# Key.net
KiCad netlist of a schematic drawn in Altium Designer
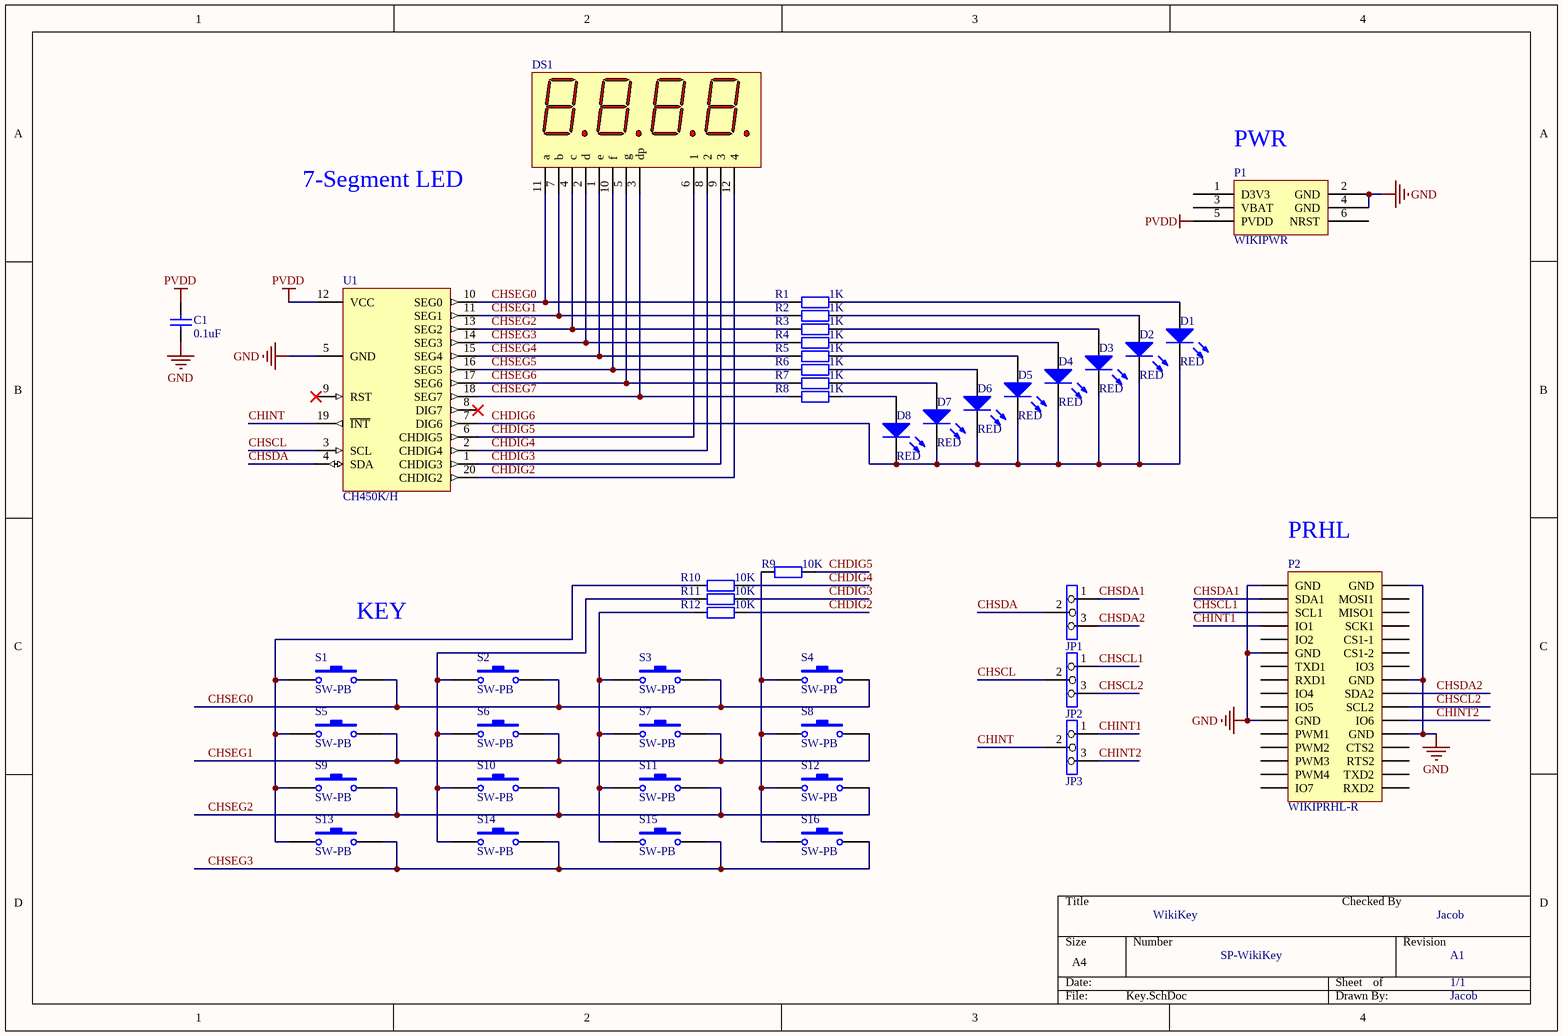
[diagram p0: Key.SchDoc]

(export (version "E")
  (design (tool "Eeschema 10.0.6"))
  (components
    (comp (ref "C1")
      (value "0.1uF")
      (footprint "0603M")
      (description "Capacitor")
      (fields (field (name "PUBLISHER") "Altium Limited"))
      (libsource (lib "Miscellaneous Devices") (part "Cap"))
    )
    (comp (ref "D1")
      (value "RED")
      (footprint "0603pn")
      (description "Typical INFRARED GaAs LED")
      (fields (field (name "PUBLISHER") "Altium Limited"))
      (libsource (lib "Miscellaneous Devices") (part "LED0"))
    )
    (comp (ref "D2")
      (value "RED")
      (footprint "0603pn")
      (description "Typical INFRARED GaAs LED")
      (fields (field (name "PUBLISHER") "Altium Limited"))
      (libsource (lib "Miscellaneous Devices") (part "LED0"))
    )
    (comp (ref "D3")
      (value "RED")
      (footprint "0603pn")
      (description "Typical INFRARED GaAs LED")
      (fields (field (name "PUBLISHER") "Altium Limited"))
      (libsource (lib "Miscellaneous Devices") (part "LED0"))
    )
    (comp (ref "D4")
      (value "RED")
      (footprint "0603pn")
      (description "Typical INFRARED GaAs LED")
      (fields (field (name "PUBLISHER") "Altium Limited"))
      (libsource (lib "Miscellaneous Devices") (part "LED0"))
    )
    (comp (ref "D5")
      (value "RED")
      (footprint "0603pn")
      (description "Typical INFRARED GaAs LED")
      (fields (field (name "PUBLISHER") "Altium Limited"))
      (libsource (lib "Miscellaneous Devices") (part "LED0"))
    )
    (comp (ref "D6")
      (value "RED")
      (footprint "0603pn")
      (description "Typical INFRARED GaAs LED")
      (fields (field (name "PUBLISHER") "Altium Limited"))
      (libsource (lib "Miscellaneous Devices") (part "LED0"))
    )
    (comp (ref "D7")
      (value "RED")
      (footprint "0603pn")
      (description "Typical INFRARED GaAs LED")
      (fields (field (name "PUBLISHER") "Altium Limited"))
      (libsource (lib "Miscellaneous Devices") (part "LED0"))
    )
    (comp (ref "D8")
      (value "RED")
      (footprint "0603pn")
      (description "Typical INFRARED GaAs LED")
      (fields (field (name "PUBLISHER") "Altium Limited"))
      (libsource (lib "Miscellaneous Devices") (part "LED0"))
    )
    (comp (ref "DS1")
      (value "7SEG-4")
      (footprint "7SGLED-4-0.28")
      (description "Black Surface HER 7-Segment Display")
      (fields (field (name "PUBLISHER") "Altium Limited"))
      (libsource (lib "Misc") (part "7SEG-4"))
    )
    (comp (ref "JP1") (value "Jumper3") (footprint "HDR1X3/2.54MM") (libsource (lib "Misc") (part "Jumper3")))
    (comp (ref "JP2") (value "Jumper3") (footprint "HDR1X3/2.54MM") (libsource (lib "Misc") (part "Jumper3")))
    (comp (ref "JP3") (value "Jumper3") (footprint "HDR1X3/2.54MM") (libsource (lib "Misc") (part "Jumper3")))
    (comp (ref "P1")
      (value "WIKIPWR")
      (footprint "WIKIPWR")
      (description "PWR HDR")
      (libsource (lib "Connector") (part "WIKIPWR"))
    )
    (comp (ref "P2")
      (value "WIKIPRHL-R")
      (footprint "HDR2X16-WIKIPRHL-R")
      (description "Header, 16-Pin, Dual row")
      (fields (field (name "PUBLISHER") "Altium Limited"))
      (libsource (lib "Connector") (part "WIKIPRHL-R"))
    )
    (comp (ref "R1")
      (value "1K")
      (footprint "0603M")
      (description "Resistor")
      (fields (field (name "PUBLISHER") "Altium Limited"))
      (libsource (lib "Miscellaneous Devices") (part "Res2"))
    )
    (comp (ref "R2")
      (value "1K")
      (footprint "0603M")
      (description "Resistor")
      (fields (field (name "PUBLISHER") "Altium Limited"))
      (libsource (lib "Miscellaneous Devices") (part "Res2"))
    )
    (comp (ref "R3")
      (value "1K")
      (footprint "0603M")
      (description "Resistor")
      (fields (field (name "PUBLISHER") "Altium Limited"))
      (libsource (lib "Miscellaneous Devices") (part "Res2"))
    )
    (comp (ref "R4")
      (value "1K")
      (footprint "0603M")
      (description "Resistor")
      (fields (field (name "PUBLISHER") "Altium Limited"))
      (libsource (lib "Miscellaneous Devices") (part "Res2"))
    )
    (comp (ref "R5")
      (value "1K")
      (footprint "0603M")
      (description "Resistor")
      (fields (field (name "PUBLISHER") "Altium Limited"))
      (libsource (lib "Miscellaneous Devices") (part "Res2"))
    )
    (comp (ref "R6")
      (value "1K")
      (footprint "0603M")
      (description "Resistor")
      (fields (field (name "PUBLISHER") "Altium Limited"))
      (libsource (lib "Miscellaneous Devices") (part "Res2"))
    )
    (comp (ref "R7")
      (value "1K")
      (footprint "0603M")
      (description "Resistor")
      (fields (field (name "PUBLISHER") "Altium Limited"))
      (libsource (lib "Miscellaneous Devices") (part "Res2"))
    )
    (comp (ref "R8")
      (value "1K")
      (footprint "0603M")
      (description "Resistor")
      (fields (field (name "PUBLISHER") "Altium Limited"))
      (libsource (lib "Miscellaneous Devices") (part "Res2"))
    )
    (comp (ref "R9")
      (value "10K")
      (footprint "0603M")
      (description "Resistor")
      (fields (field (name "PUBLISHER") "Altium Limited"))
      (libsource (lib "Miscellaneous Devices") (part "Res2"))
    )
    (comp (ref "R10")
      (value "10K")
      (footprint "0603M")
      (description "Resistor")
      (fields (field (name "PUBLISHER") "Altium Limited"))
      (libsource (lib "Miscellaneous Devices") (part "Res2"))
    )
    (comp (ref "R11")
      (value "10K")
      (footprint "0603M")
      (description "Resistor")
      (fields (field (name "PUBLISHER") "Altium Limited"))
      (libsource (lib "Miscellaneous Devices") (part "Res2"))
    )
    (comp (ref "R12")
      (value "10K")
      (footprint "0603M")
      (description "Resistor")
      (fields (field (name "PUBLISHER") "Altium Limited"))
      (libsource (lib "Miscellaneous Devices") (part "Res2"))
    )
    (comp (ref "S1")
      (value "SW-PB")
      (footprint "KEY-4.5X4.5-SMD")
      (description "Switch")
      (fields (field (name "PUBLISHER") "Altium Limited"))
      (libsource (lib "CT107D_SUDA") (part "SW-PB"))
    )
    (comp (ref "S2")
      (value "SW-PB")
      (footprint "KEY-4.5X4.5-SMD")
      (description "Switch")
      (fields (field (name "PUBLISHER") "Altium Limited"))
      (libsource (lib "CT107D_SUDA") (part "SW-PB"))
    )
    (comp (ref "S3")
      (value "SW-PB")
      (footprint "KEY-4.5X4.5-SMD")
      (description "Switch")
      (fields (field (name "PUBLISHER") "Altium Limited"))
      (libsource (lib "CT107D_SUDA") (part "SW-PB"))
    )
    (comp (ref "S4")
      (value "SW-PB")
      (footprint "KEY-4.5X4.5-SMD")
      (description "Switch")
      (fields (field (name "PUBLISHER") "Altium Limited"))
      (libsource (lib "CT107D_SUDA") (part "SW-PB"))
    )
    (comp (ref "S5")
      (value "SW-PB")
      (footprint "KEY-4.5X4.5-SMD")
      (description "Switch")
      (fields (field (name "PUBLISHER") "Altium Limited"))
      (libsource (lib "CT107D_SUDA") (part "SW-PB"))
    )
    (comp (ref "S6")
      (value "SW-PB")
      (footprint "KEY-4.5X4.5-SMD")
      (description "Switch")
      (fields (field (name "PUBLISHER") "Altium Limited"))
      (libsource (lib "CT107D_SUDA") (part "SW-PB"))
    )
    (comp (ref "S7")
      (value "SW-PB")
      (footprint "KEY-4.5X4.5-SMD")
      (description "Switch")
      (fields (field (name "PUBLISHER") "Altium Limited"))
      (libsource (lib "CT107D_SUDA") (part "SW-PB"))
    )
    (comp (ref "S8")
      (value "SW-PB")
      (footprint "KEY-4.5X4.5-SMD")
      (description "Switch")
      (fields (field (name "PUBLISHER") "Altium Limited"))
      (libsource (lib "CT107D_SUDA") (part "SW-PB"))
    )
    (comp (ref "S9")
      (value "SW-PB")
      (footprint "KEY-4.5X4.5-SMD")
      (description "Switch")
      (fields (field (name "PUBLISHER") "Altium Limited"))
      (libsource (lib "CT107D_SUDA") (part "SW-PB"))
    )
    (comp (ref "S10")
      (value "SW-PB")
      (footprint "KEY-4.5X4.5-SMD")
      (description "Switch")
      (fields (field (name "PUBLISHER") "Altium Limited"))
      (libsource (lib "CT107D_SUDA") (part "SW-PB"))
    )
    (comp (ref "S11")
      (value "SW-PB")
      (footprint "KEY-4.5X4.5-SMD")
      (description "Switch")
      (fields (field (name "PUBLISHER") "Altium Limited"))
      (libsource (lib "CT107D_SUDA") (part "SW-PB"))
    )
    (comp (ref "S12")
      (value "SW-PB")
      (footprint "KEY-4.5X4.5-SMD")
      (description "Switch")
      (fields (field (name "PUBLISHER") "Altium Limited"))
      (libsource (lib "CT107D_SUDA") (part "SW-PB"))
    )
    (comp (ref "S13")
      (value "SW-PB")
      (footprint "KEY-4.5X4.5-SMD")
      (description "Switch")
      (fields (field (name "PUBLISHER") "Altium Limited"))
      (libsource (lib "CT107D_SUDA") (part "SW-PB"))
    )
    (comp (ref "S14")
      (value "SW-PB")
      (footprint "KEY-4.5X4.5-SMD")
      (description "Switch")
      (fields (field (name "PUBLISHER") "Altium Limited"))
      (libsource (lib "CT107D_SUDA") (part "SW-PB"))
    )
    (comp (ref "S15")
      (value "SW-PB")
      (footprint "KEY-4.5X4.5-SMD")
      (description "Switch")
      (fields (field (name "PUBLISHER") "Altium Limited"))
      (libsource (lib "CT107D_SUDA") (part "SW-PB"))
    )
    (comp (ref "S16")
      (value "SW-PB")
      (footprint "KEY-4.5X4.5-SMD")
      (description "Switch")
      (fields (field (name "PUBLISHER") "Altium Limited"))
      (libsource (lib "CT107D_SUDA") (part "SW-PB"))
    )
    (comp (ref "U1")
      (value "CH450K/H")
      (footprint "SO20W_M")
      (description "7 Segment LED& Key")
      (libsource (lib "Lunio") (part "CH450K/H"))
    )
  )
  (nets
    (net (code "1") (name "/CHDIG2") (class "Default")
      (node (ref "DS1") (pin "12") (pinfunction "4_12") (pintype "passive"))
      (node (ref "R12") (pin "1") (pinfunction "1_1") (pintype "passive"))
      (node (ref "U1") (pin "20") (pinfunction "CHDIG2_20") (pintype "output"))
    )
    (net (code "2") (name "/CHDIG3") (class "Default")
      (node (ref "DS1") (pin "9") (pinfunction "3_9") (pintype "passive"))
      (node (ref "R11") (pin "1") (pinfunction "1_1") (pintype "passive"))
      (node (ref "U1") (pin "1") (pinfunction "CHDIG3_1") (pintype "output"))
    )
    (net (code "3") (name "/CHDIG4") (class "Default")
      (node (ref "DS1") (pin "8") (pinfunction "2_8") (pintype "passive"))
      (node (ref "R10") (pin "1") (pinfunction "1_1") (pintype "passive"))
      (node (ref "U1") (pin "2") (pinfunction "CHDIG4_2") (pintype "output"))
    )
    (net (code "4") (name "/CHDIG5") (class "Default")
      (node (ref "DS1") (pin "6") (pinfunction "1_6") (pintype "passive"))
      (node (ref "R9") (pin "1") (pinfunction "1_1") (pintype "passive"))
      (node (ref "U1") (pin "6") (pinfunction "CHDIG5_6") (pintype "output"))
    )
    (net (code "5") (name "/CHDIG6") (class "Default")
      (node (ref "D1") (pin "2") (pinfunction "K_2") (pintype "passive"))
      (node (ref "D2") (pin "2") (pinfunction "K_2") (pintype "passive"))
      (node (ref "D3") (pin "2") (pinfunction "K_2") (pintype "passive"))
      (node (ref "D4") (pin "2") (pinfunction "K_2") (pintype "passive"))
      (node (ref "D5") (pin "2") (pinfunction "K_2") (pintype "passive"))
      (node (ref "D6") (pin "2") (pinfunction "K_2") (pintype "passive"))
      (node (ref "D7") (pin "2") (pinfunction "K_2") (pintype "passive"))
      (node (ref "D8") (pin "2") (pinfunction "K_2") (pintype "passive"))
      (node (ref "U1") (pin "7") (pinfunction "DIG6_7") (pintype "output"))
    )
    (net (code "6") (name "/CHINT") (class "Default")
      (node (ref "JP3") (pin "2") (pintype "passive"))
      (node (ref "U1") (pin "19") (pinfunction "~{INT}_19") (pintype "output"))
    )
    (net (code "7") (name "/CHINT1") (class "Default")
      (node (ref "JP3") (pin "1") (pintype "passive"))
      (node (ref "P2") (pin "7") (pinfunction "IO1_7") (pintype "passive"))
    )
    (net (code "8") (name "/CHINT2") (class "Default")
      (node (ref "JP3") (pin "3") (pintype "passive"))
      (node (ref "P2") (pin "22") (pinfunction "IO6_22") (pintype "passive"))
    )
    (net (code "9") (name "/CHSCL") (class "Default")
      (node (ref "JP2") (pin "2") (pintype "passive"))
      (node (ref "U1") (pin "3") (pinfunction "SCL_3") (pintype "input"))
    )
    (net (code "10") (name "/CHSCL1") (class "Default")
      (node (ref "JP2") (pin "1") (pintype "passive"))
      (node (ref "P2") (pin "5") (pinfunction "SCL1_5") (pintype "passive"))
    )
    (net (code "11") (name "/CHSCL2") (class "Default")
      (node (ref "JP2") (pin "3") (pintype "passive"))
      (node (ref "P2") (pin "20") (pinfunction "SCL2_20") (pintype "passive"))
    )
    (net (code "12") (name "/CHSDA") (class "Default")
      (node (ref "JP1") (pin "2") (pintype "passive"))
      (node (ref "U1") (pin "4") (pinfunction "SDA_4") (pintype "bidirectional"))
    )
    (net (code "13") (name "/CHSDA1") (class "Default")
      (node (ref "JP1") (pin "1") (pintype "passive"))
      (node (ref "P2") (pin "3") (pinfunction "SDA1_3") (pintype "passive"))
    )
    (net (code "14") (name "/CHSDA2") (class "Default")
      (node (ref "JP1") (pin "3") (pintype "passive"))
      (node (ref "P2") (pin "18") (pinfunction "SDA2_18") (pintype "passive"))
    )
    (net (code "15") (name "/CHSEG0") (class "Default")
      (node (ref "DS1") (pin "11") (pinfunction "a_11") (pintype "passive"))
      (node (ref "R1") (pin "2") (pinfunction "2_2") (pintype "passive"))
      (node (ref "S1") (pin "2") (pinfunction "2_2") (pintype "passive"))
      (node (ref "S2") (pin "2") (pinfunction "2_2") (pintype "passive"))
      (node (ref "S3") (pin "2") (pinfunction "2_2") (pintype "passive"))
      (node (ref "S4") (pin "2") (pinfunction "2_2") (pintype "passive"))
      (node (ref "U1") (pin "10") (pinfunction "SEG0_10") (pintype "output"))
    )
    (net (code "16") (name "/CHSEG1") (class "Default")
      (node (ref "DS1") (pin "7") (pinfunction "b_7") (pintype "passive"))
      (node (ref "R2") (pin "2") (pinfunction "2_2") (pintype "passive"))
      (node (ref "S5") (pin "2") (pinfunction "2_2") (pintype "passive"))
      (node (ref "S6") (pin "2") (pinfunction "2_2") (pintype "passive"))
      (node (ref "S7") (pin "2") (pinfunction "2_2") (pintype "passive"))
      (node (ref "S8") (pin "2") (pinfunction "2_2") (pintype "passive"))
      (node (ref "U1") (pin "11") (pinfunction "SEG1_11") (pintype "output"))
    )
    (net (code "17") (name "/CHSEG2") (class "Default")
      (node (ref "DS1") (pin "4") (pinfunction "c_4") (pintype "passive"))
      (node (ref "R3") (pin "2") (pinfunction "2_2") (pintype "passive"))
      (node (ref "S10") (pin "2") (pinfunction "2_2") (pintype "passive"))
      (node (ref "S11") (pin "2") (pinfunction "2_2") (pintype "passive"))
      (node (ref "S12") (pin "2") (pinfunction "2_2") (pintype "passive"))
      (node (ref "S9") (pin "2") (pinfunction "2_2") (pintype "passive"))
      (node (ref "U1") (pin "13") (pinfunction "SEG2_13") (pintype "output"))
    )
    (net (code "18") (name "/CHSEG3") (class "Default")
      (node (ref "DS1") (pin "2") (pinfunction "d_2") (pintype "passive"))
      (node (ref "R4") (pin "2") (pinfunction "2_2") (pintype "passive"))
      (node (ref "S13") (pin "2") (pinfunction "2_2") (pintype "passive"))
      (node (ref "S14") (pin "2") (pinfunction "2_2") (pintype "passive"))
      (node (ref "S15") (pin "2") (pinfunction "2_2") (pintype "passive"))
      (node (ref "S16") (pin "2") (pinfunction "2_2") (pintype "passive"))
      (node (ref "U1") (pin "14") (pinfunction "SEG3_14") (pintype "output"))
    )
    (net (code "19") (name "/CHSEG4") (class "Default")
      (node (ref "DS1") (pin "1") (pinfunction "e_1") (pintype "passive"))
      (node (ref "R5") (pin "2") (pinfunction "2_2") (pintype "passive"))
      (node (ref "U1") (pin "15") (pinfunction "SEG4_15") (pintype "output"))
    )
    (net (code "20") (name "/CHSEG5") (class "Default")
      (node (ref "DS1") (pin "10") (pinfunction "f_10") (pintype "passive"))
      (node (ref "R6") (pin "2") (pinfunction "2_2") (pintype "passive"))
      (node (ref "U1") (pin "16") (pinfunction "SEG5_16") (pintype "output"))
    )
    (net (code "21") (name "/CHSEG6") (class "Default")
      (node (ref "DS1") (pin "5") (pinfunction "g_5") (pintype "passive"))
      (node (ref "R7") (pin "2") (pinfunction "2_2") (pintype "passive"))
      (node (ref "U1") (pin "17") (pinfunction "SEG6_17") (pintype "output"))
    )
    (net (code "22") (name "/CHSEG7") (class "Default")
      (node (ref "DS1") (pin "3") (pinfunction "dp_3") (pintype "passive"))
      (node (ref "R8") (pin "2") (pinfunction "2_2") (pintype "passive"))
      (node (ref "U1") (pin "18") (pinfunction "SEG7_18") (pintype "output"))
    )
    (net (code "23") (name "GND") (class "Default")
      (node (ref "C1") (pin "1") (pinfunction "1_1") (pintype "passive"))
      (node (ref "P1") (pin "2") (pinfunction "GND_2") (pintype "passive"))
      (node (ref "P1") (pin "4") (pinfunction "GND_4") (pintype "passive"))
      (node (ref "P2") (pin "1") (pinfunction "GND_1") (pintype "passive"))
      (node (ref "P2") (pin "11") (pinfunction "GND_11") (pintype "passive"))
      (node (ref "P2") (pin "16") (pinfunction "GND_16") (pintype "passive"))
      (node (ref "P2") (pin "2") (pinfunction "GND_2") (pintype "passive"))
      (node (ref "P2") (pin "21") (pinfunction "GND_21") (pintype "passive"))
      (node (ref "P2") (pin "24") (pinfunction "GND_24") (pintype "passive"))
      (node (ref "U1") (pin "5") (pinfunction "GND_5") (pintype "power_in"))
    )
    (net (code "24") (name "Net-(D1-A)") (class "Default")
      (node (ref "D1") (pin "1") (pinfunction "A_1") (pintype "passive"))
      (node (ref "R1") (pin "1") (pinfunction "1_1") (pintype "passive"))
    )
    (net (code "25") (name "Net-(D2-A)") (class "Default")
      (node (ref "D2") (pin "1") (pinfunction "A_1") (pintype "passive"))
      (node (ref "R2") (pin "1") (pinfunction "1_1") (pintype "passive"))
    )
    (net (code "26") (name "Net-(D3-A)") (class "Default")
      (node (ref "D3") (pin "1") (pinfunction "A_1") (pintype "passive"))
      (node (ref "R3") (pin "1") (pinfunction "1_1") (pintype "passive"))
    )
    (net (code "27") (name "Net-(D4-A)") (class "Default")
      (node (ref "D4") (pin "1") (pinfunction "A_1") (pintype "passive"))
      (node (ref "R4") (pin "1") (pinfunction "1_1") (pintype "passive"))
    )
    (net (code "28") (name "Net-(D5-A)") (class "Default")
      (node (ref "D5") (pin "1") (pinfunction "A_1") (pintype "passive"))
      (node (ref "R5") (pin "1") (pinfunction "1_1") (pintype "passive"))
    )
    (net (code "29") (name "Net-(D6-A)") (class "Default")
      (node (ref "D6") (pin "1") (pinfunction "A_1") (pintype "passive"))
      (node (ref "R6") (pin "1") (pinfunction "1_1") (pintype "passive"))
    )
    (net (code "30") (name "Net-(D7-A)") (class "Default")
      (node (ref "D7") (pin "1") (pinfunction "A_1") (pintype "passive"))
      (node (ref "R7") (pin "1") (pinfunction "1_1") (pintype "passive"))
    )
    (net (code "31") (name "Net-(D8-A)") (class "Default")
      (node (ref "D8") (pin "1") (pinfunction "A_1") (pintype "passive"))
      (node (ref "R8") (pin "1") (pinfunction "1_1") (pintype "passive"))
    )
    (net (code "32") (name "Net-(R9-Pad2)") (class "Default")
      (node (ref "R9") (pin "2") (pinfunction "2_2") (pintype "passive"))
      (node (ref "S12") (pin "1") (pinfunction "1_1") (pintype "passive"))
      (node (ref "S16") (pin "1") (pinfunction "1_1") (pintype "passive"))
      (node (ref "S4") (pin "1") (pinfunction "1_1") (pintype "passive"))
      (node (ref "S8") (pin "1") (pinfunction "1_1") (pintype "passive"))
    )
    (net (code "33") (name "Net-(R10-Pad2)") (class "Default")
      (node (ref "R10") (pin "2") (pinfunction "2_2") (pintype "passive"))
      (node (ref "S1") (pin "1") (pinfunction "1_1") (pintype "passive"))
      (node (ref "S13") (pin "1") (pinfunction "1_1") (pintype "passive"))
      (node (ref "S5") (pin "1") (pinfunction "1_1") (pintype "passive"))
      (node (ref "S9") (pin "1") (pinfunction "1_1") (pintype "passive"))
    )
    (net (code "34") (name "Net-(R11-Pad2)") (class "Default")
      (node (ref "R11") (pin "2") (pinfunction "2_2") (pintype "passive"))
      (node (ref "S10") (pin "1") (pinfunction "1_1") (pintype "passive"))
      (node (ref "S14") (pin "1") (pinfunction "1_1") (pintype "passive"))
      (node (ref "S2") (pin "1") (pinfunction "1_1") (pintype "passive"))
      (node (ref "S6") (pin "1") (pinfunction "1_1") (pintype "passive"))
    )
    (net (code "35") (name "Net-(R12-Pad2)") (class "Default")
      (node (ref "R12") (pin "2") (pinfunction "2_2") (pintype "passive"))
      (node (ref "S11") (pin "1") (pinfunction "1_1") (pintype "passive"))
      (node (ref "S15") (pin "1") (pinfunction "1_1") (pintype "passive"))
      (node (ref "S3") (pin "1") (pinfunction "1_1") (pintype "passive"))
      (node (ref "S7") (pin "1") (pinfunction "1_1") (pintype "passive"))
    )
    (net (code "36") (name "PVDD") (class "Default")
      (node (ref "C1") (pin "2") (pinfunction "2_2") (pintype "passive"))
      (node (ref "P1") (pin "5") (pinfunction "PVDD_5") (pintype "passive"))
      (node (ref "U1") (pin "12") (pinfunction "VCC_12") (pintype "power_in"))
    )
    (net (code "37") (name "unconnected-(P1-D3V3-Pad1)") (class "Default")
      (node (ref "P1") (pin "1") (pinfunction "D3V3_1") (pintype "passive"))
    )
    (net (code "38") (name "unconnected-(P1-NRST-Pad6)") (class "Default")
      (node (ref "P1") (pin "6") (pinfunction "NRST_6") (pintype "passive"))
    )
    (net (code "39") (name "unconnected-(P1-VBAT-Pad3)") (class "Default")
      (node (ref "P1") (pin "3") (pinfunction "VBAT_3") (pintype "passive"))
    )
    (net (code "40") (name "unconnected-(P2-CS1-1-Pad10)") (class "Default")
      (node (ref "P2") (pin "10") (pinfunction "CS1-1_10") (pintype "passive"))
    )
    (net (code "41") (name "unconnected-(P2-CS1-2-Pad12)") (class "Default")
      (node (ref "P2") (pin "12") (pinfunction "CS1-2_12") (pintype "passive"))
    )
    (net (code "42") (name "unconnected-(P2-CTS2-Pad26)") (class "Default")
      (node (ref "P2") (pin "26") (pinfunction "CTS2_26") (pintype "passive"))
    )
    (net (code "43") (name "unconnected-(P2-IO2-Pad9)") (class "Default")
      (node (ref "P2") (pin "9") (pinfunction "IO2_9") (pintype "passive"))
    )
    (net (code "44") (name "unconnected-(P2-IO3-Pad14)") (class "Default")
      (node (ref "P2") (pin "14") (pinfunction "IO3_14") (pintype "passive"))
    )
    (net (code "45") (name "unconnected-(P2-IO4-Pad17)") (class "Default")
      (node (ref "P2") (pin "17") (pinfunction "IO4_17") (pintype "passive"))
    )
    (net (code "46") (name "unconnected-(P2-IO5-Pad19)") (class "Default")
      (node (ref "P2") (pin "19") (pinfunction "IO5_19") (pintype "passive"))
    )
    (net (code "47") (name "unconnected-(P2-IO7-Pad31)") (class "Default")
      (node (ref "P2") (pin "31") (pinfunction "IO7_31") (pintype "passive"))
    )
    (net (code "48") (name "unconnected-(P2-MISO1-Pad6)") (class "Default")
      (node (ref "P2") (pin "6") (pinfunction "MISO1_6") (pintype "passive"))
    )
    (net (code "49") (name "unconnected-(P2-MOSI1-Pad4)") (class "Default")
      (node (ref "P2") (pin "4") (pinfunction "MOSI1_4") (pintype "passive"))
    )
    (net (code "50") (name "unconnected-(P2-PWM1-Pad23)") (class "Default")
      (node (ref "P2") (pin "23") (pinfunction "PWM1_23") (pintype "passive"))
    )
    (net (code "51") (name "unconnected-(P2-PWM2-Pad25)") (class "Default")
      (node (ref "P2") (pin "25") (pinfunction "PWM2_25") (pintype "passive"))
    )
    (net (code "52") (name "unconnected-(P2-PWM3-Pad27)") (class "Default")
      (node (ref "P2") (pin "27") (pinfunction "PWM3_27") (pintype "passive"))
    )
    (net (code "53") (name "unconnected-(P2-PWM4-Pad29)") (class "Default")
      (node (ref "P2") (pin "29") (pinfunction "PWM4_29") (pintype "passive"))
    )
    (net (code "54") (name "unconnected-(P2-RTS2-Pad28)") (class "Default")
      (node (ref "P2") (pin "28") (pinfunction "RTS2_28") (pintype "passive"))
    )
    (net (code "55") (name "unconnected-(P2-RXD1-Pad15)") (class "Default")
      (node (ref "P2") (pin "15") (pinfunction "RXD1_15") (pintype "passive"))
    )
    (net (code "56") (name "unconnected-(P2-RXD2-Pad32)") (class "Default")
      (node (ref "P2") (pin "32") (pinfunction "RXD2_32") (pintype "passive"))
    )
    (net (code "57") (name "unconnected-(P2-SCK1-Pad8)") (class "Default")
      (node (ref "P2") (pin "8") (pinfunction "SCK1_8") (pintype "passive"))
    )
    (net (code "58") (name "unconnected-(P2-TXD1-Pad13)") (class "Default")
      (node (ref "P2") (pin "13") (pinfunction "TXD1_13") (pintype "passive"))
    )
    (net (code "59") (name "unconnected-(P2-TXD2-Pad30)") (class "Default")
      (node (ref "P2") (pin "30") (pinfunction "TXD2_30") (pintype "passive"))
    )
    (net (code "60") (name "unconnected-(U1-DIG7-Pad8)") (class "Default")
      (node (ref "U1") (pin "8") (pinfunction "DIG7_8") (pintype "output+no_connect"))
    )
    (net (code "61") (name "unconnected-(U1-RST-Pad9)") (class "Default")
      (node (ref "U1") (pin "9") (pinfunction "RST_9") (pintype "input+no_connect"))
    )
  )
)
